# ESP-01_prog_v1_0.net
KiCad netlist of a schematic drawn in EAGLE
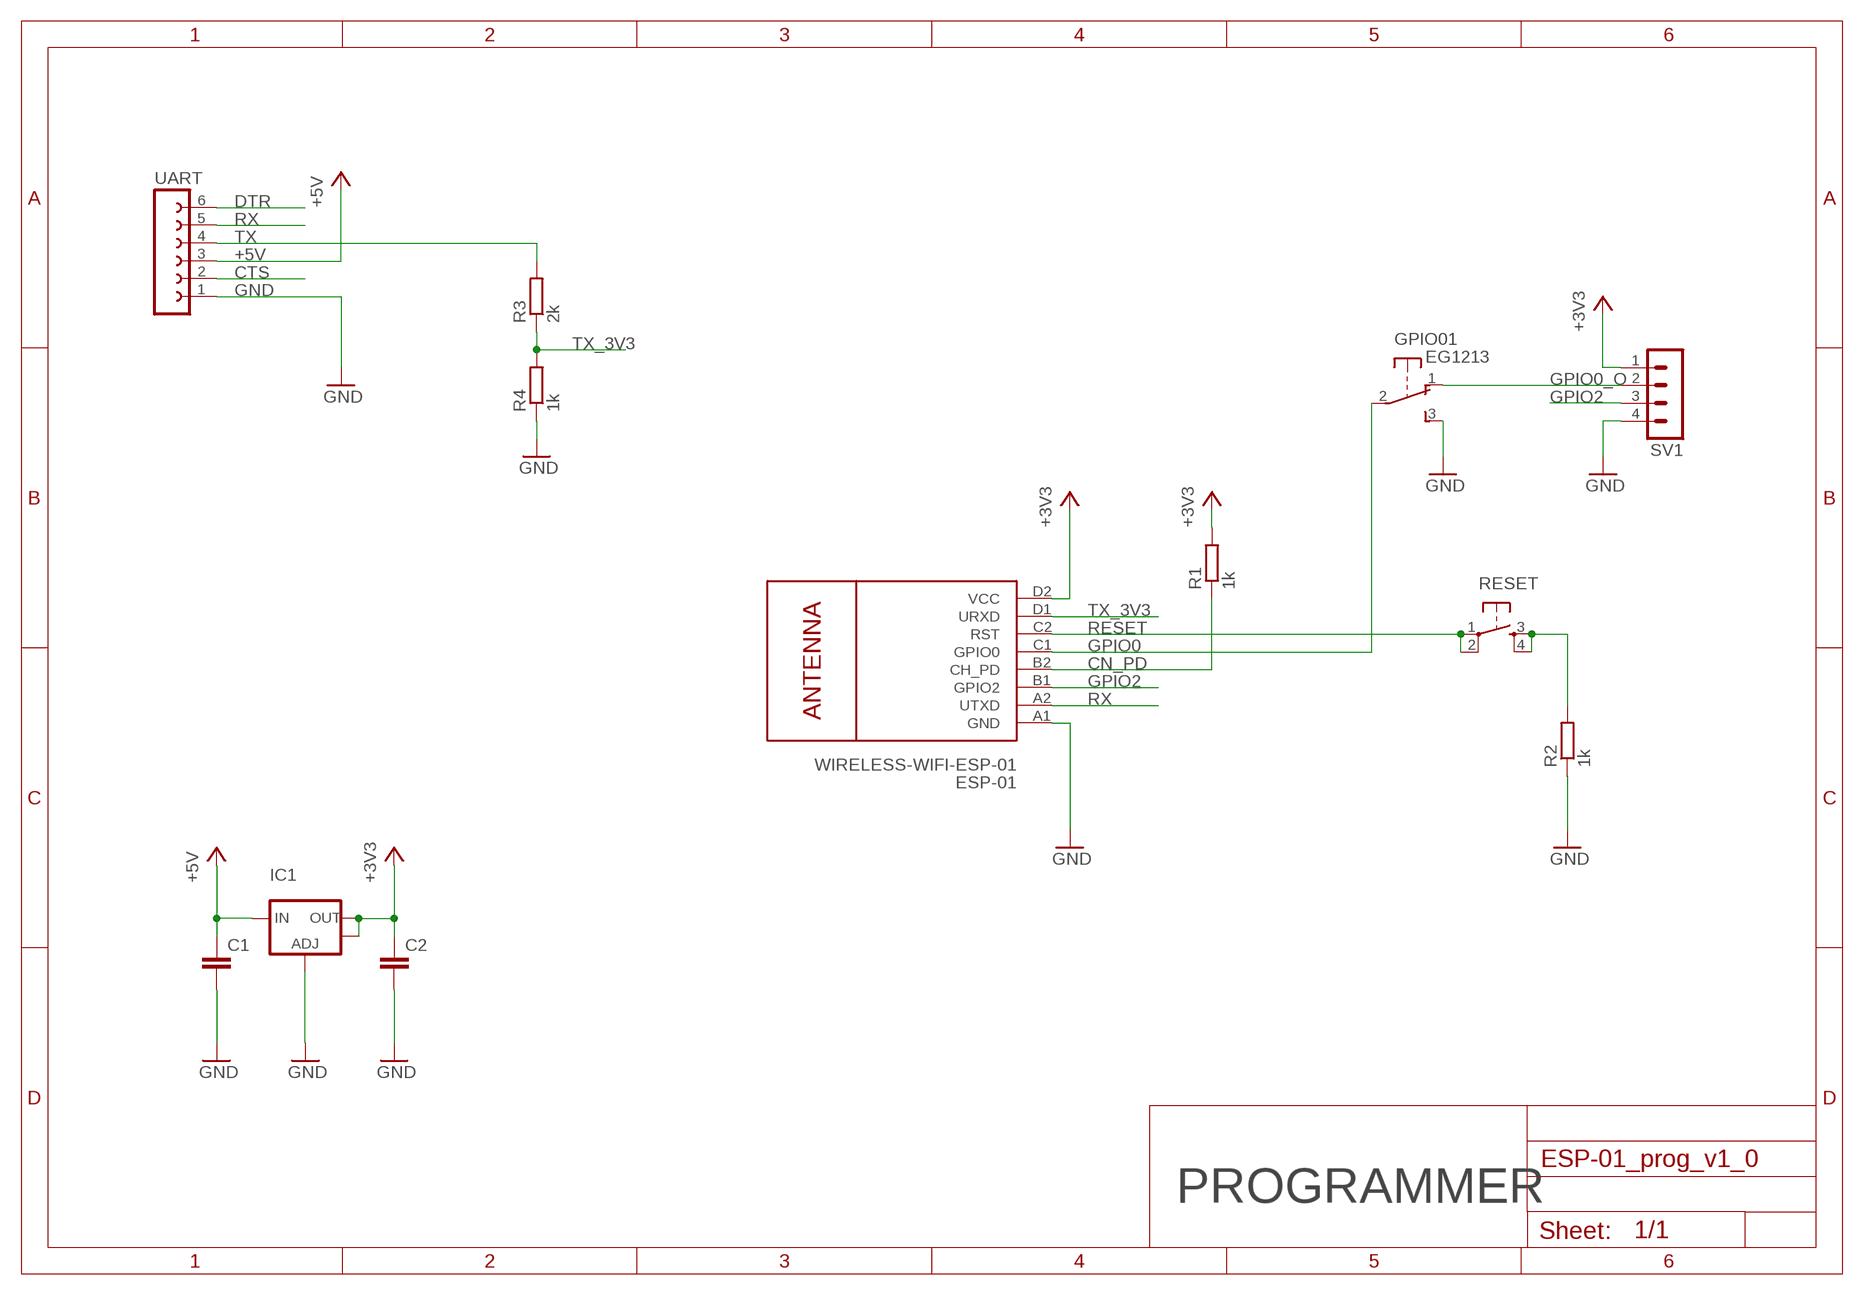
[diagram p0: schematic, sheet 1]

(export (version "E")
  (design (tool "Eeschema 10.0.6"))
  (components
    (comp (ref "C1")
      (value "C-EUC0603")
      (footprint "eagle-import:C0603")
      (libsource (lib "eagle-import") (part "C-EUC0603"))
    )
    (comp (ref "C2")
      (value "C-EUC0603")
      (footprint "eagle-import:C0603")
      (libsource (lib "eagle-import") (part "C-EUC0603"))
    )
    (comp (ref "ESP-01")
      (value "WIRELESS-WIFI-ESP-01")
      (footprint "eagle-import:WIRELESS-WIFI-ESP-01")
      (libsource (lib "eagle-import") (part "WIRELESS-WIFI-ESP-01"))
    )
    (comp (ref "GPIO0")
      (value "EG1213")
      (footprint "eagle-import:EG1213")
      (libsource (lib "eagle-import") (part "EG1213"))
    )
    (comp (ref "IC1")
      (value "LM1117SOT223")
      (footprint "eagle-import:SOT223")
      (libsource (lib "eagle-import") (part "LM1117SOT223"))
    )
    (comp (ref "R1")
      (value "1k")
      (footprint "eagle-import:R0603")
      (libsource (lib "eagle-import") (part "R-EU_R0603"))
    )
    (comp (ref "R2")
      (value "1k")
      (footprint "eagle-import:R0603")
      (libsource (lib "eagle-import") (part "R-EU_R0603"))
    )
    (comp (ref "R3")
      (value "2k")
      (footprint "eagle-import:R0603")
      (libsource (lib "eagle-import") (part "R-EU_R0603"))
    )
    (comp (ref "R4")
      (value "1k")
      (footprint "eagle-import:R0603")
      (libsource (lib "eagle-import") (part "R-EU_R0603"))
    )
    (comp (ref "RESET")
      (value "TAC_SWITCHPTH")
      (footprint "eagle-import:TACTILE-PTH")
      (libsource (lib "eagle-import") (part "TAC_SWITCHPTH"))
    )
    (comp (ref "SV1")
      (value "MA04-1")
      (footprint "eagle-import:MA04-1")
      (libsource (lib "eagle-import") (part "MA04-1"))
    )
    (comp (ref "UART")
      (value "FE06-1")
      (footprint "eagle-import:FE06")
      (libsource (lib "eagle-import") (part "FE06-1"))
    )
  )
  (nets
    (net (code "1") (name "+3V3") (class "Default")
      (node (ref "C2") (pin "1") (pinfunction "1_1") (pintype "passive"))
      (node (ref "ESP-01") (pin "D2") (pinfunction "VCC_D2") (pintype "power_in"))
      (node (ref "IC1") (pin "2") (pinfunction "OUT_2") (pintype "output"))
      (node (ref "IC1") (pin "4") (pinfunction "OUT_4") (pintype "output"))
      (node (ref "R1") (pin "2") (pinfunction "2_2") (pintype "passive"))
      (node (ref "SV1") (pin "1") (pinfunction "1_1") (pintype "passive"))
    )
    (net (code "2") (name "+5V") (class "Default")
      (node (ref "C1") (pin "1") (pinfunction "1_1") (pintype "passive"))
      (node (ref "IC1") (pin "3") (pinfunction "IN_3") (pintype "input"))
      (node (ref "UART") (pin "3") (pinfunction "3_3") (pintype "passive"))
    )
    (net (code "3") (name "/CN_PD") (class "Default")
      (node (ref "ESP-01") (pin "B2") (pinfunction "CH_PD_B2") (pintype "bidirectional"))
      (node (ref "R1") (pin "1") (pinfunction "1_1") (pintype "passive"))
    )
    (net (code "4") (name "/CTS") (class "Default")
      (node (ref "UART") (pin "2") (pinfunction "2_2") (pintype "passive"))
    )
    (net (code "5") (name "/DTR") (class "Default")
      (node (ref "UART") (pin "6") (pinfunction "6_6") (pintype "passive"))
    )
    (net (code "6") (name "/GPIO0") (class "Default")
      (node (ref "ESP-01") (pin "C1") (pinfunction "GPIO0_C1") (pintype "bidirectional"))
      (node (ref "GPIO0") (pin "2") (pinfunction "P_2") (pintype "passive"))
    )
    (net (code "7") (name "/GPIO0_O") (class "Default")
      (node (ref "GPIO0") (pin "1") (pinfunction "O_1") (pintype "passive"))
      (node (ref "SV1") (pin "2") (pinfunction "2_2") (pintype "passive"))
    )
    (net (code "8") (name "/GPIO2") (class "Default")
      (node (ref "ESP-01") (pin "B1") (pinfunction "GPIO2_B1") (pintype "bidirectional"))
      (node (ref "SV1") (pin "3") (pinfunction "3_3") (pintype "passive"))
    )
    (net (code "9") (name "/RESET") (class "Default")
      (node (ref "ESP-01") (pin "C2") (pinfunction "RST_C2") (pintype "bidirectional"))
      (node (ref "RESET") (pin "1") (pinfunction "1_1") (pintype "passive"))
      (node (ref "RESET") (pin "2") (pinfunction "2_2") (pintype "passive"))
    )
    (net (code "10") (name "/RX") (class "Default")
      (node (ref "ESP-01") (pin "A2") (pinfunction "UTXD_A2") (pintype "bidirectional"))
      (node (ref "UART") (pin "5") (pinfunction "5_5") (pintype "passive"))
    )
    (net (code "11") (name "/TX") (class "Default")
      (node (ref "R3") (pin "2") (pinfunction "2_2") (pintype "passive"))
      (node (ref "UART") (pin "4") (pinfunction "4_4") (pintype "passive"))
    )
    (net (code "12") (name "/TX_3V3") (class "Default")
      (node (ref "ESP-01") (pin "D1") (pinfunction "URXD_D1") (pintype "bidirectional"))
      (node (ref "R3") (pin "1") (pinfunction "1_1") (pintype "passive"))
      (node (ref "R4") (pin "2") (pinfunction "2_2") (pintype "passive"))
    )
    (net (code "13") (name "GND") (class "Default")
      (node (ref "C1") (pin "2") (pinfunction "2_2") (pintype "passive"))
      (node (ref "C2") (pin "2") (pinfunction "2_2") (pintype "passive"))
      (node (ref "ESP-01") (pin "A1") (pinfunction "GND_A1") (pintype "power_in"))
      (node (ref "GPIO0") (pin "3") (pinfunction "S_3") (pintype "passive"))
      (node (ref "IC1") (pin "1") (pinfunction "ADJ_1") (pintype "input"))
      (node (ref "R2") (pin "1") (pinfunction "1_1") (pintype "passive"))
      (node (ref "R4") (pin "1") (pinfunction "1_1") (pintype "passive"))
      (node (ref "SV1") (pin "4") (pinfunction "4_4") (pintype "passive"))
      (node (ref "UART") (pin "1") (pinfunction "1_1") (pintype "passive"))
    )
    (net (code "14") (name "Net-(R2-Pad2)") (class "Default")
      (node (ref "R2") (pin "2") (pinfunction "2_2") (pintype "passive"))
      (node (ref "RESET") (pin "3") (pinfunction "3_3") (pintype "passive"))
      (node (ref "RESET") (pin "4") (pinfunction "4_4") (pintype "passive"))
    )
  )
)
